# Power_PCB.net
KiCad netlist of a schematic drawn in Altium Designer
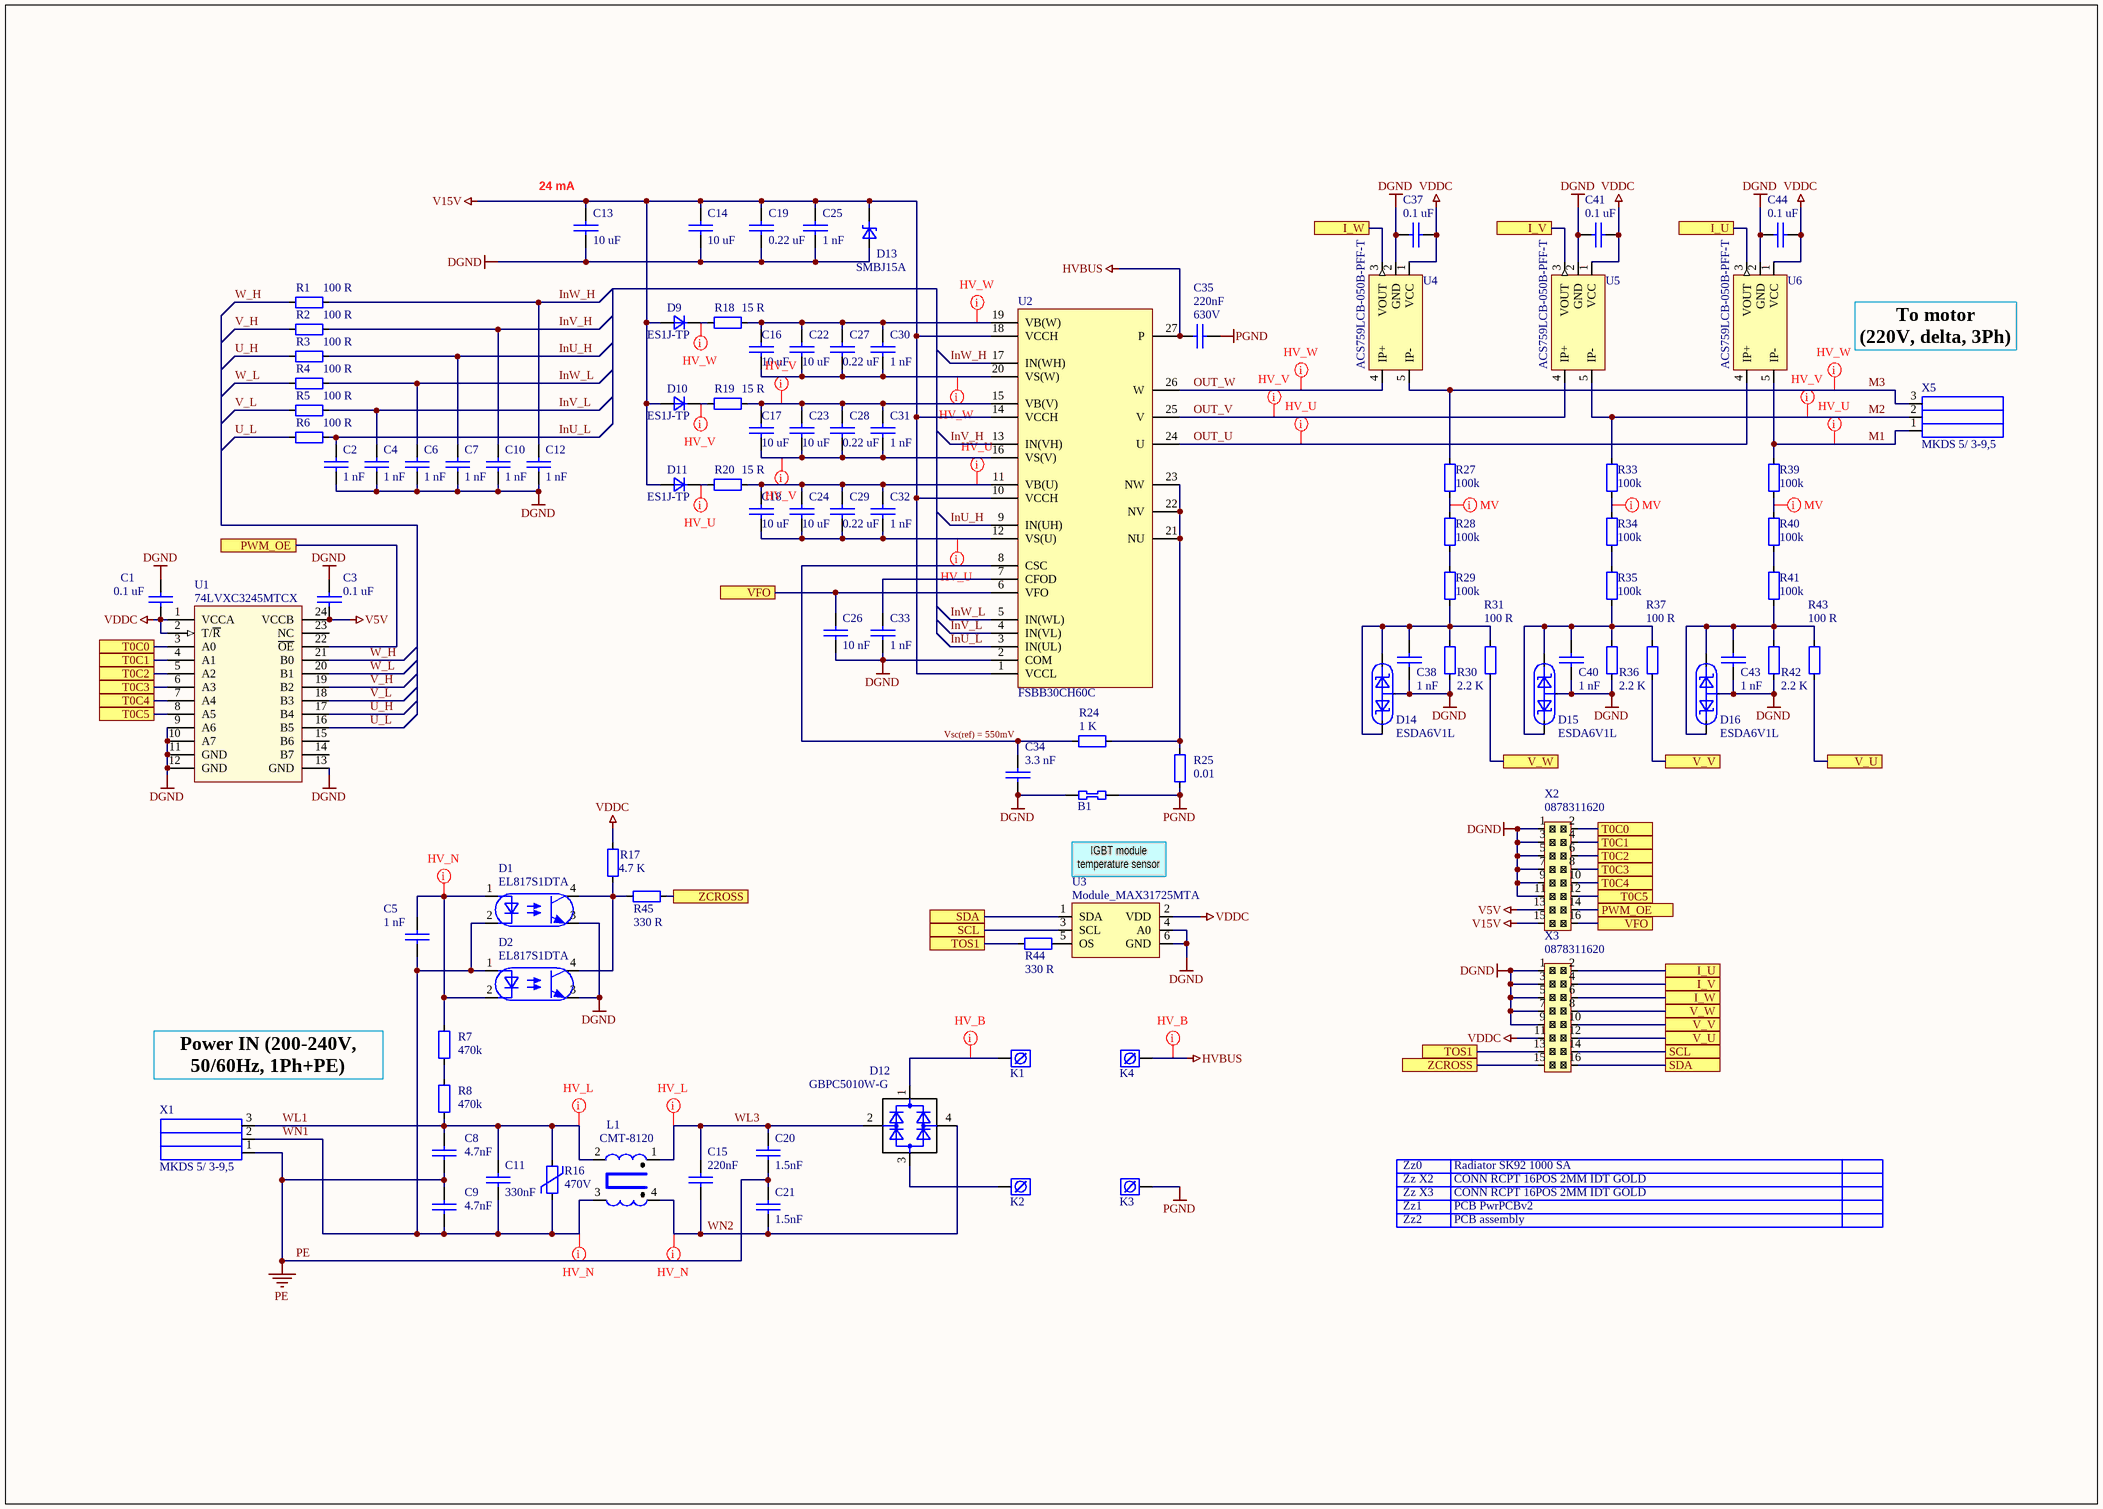
[diagram p0: Power_PCB.SchDoc]

(export (version "E")
  (design (tool "Eeschema 10.0.6"))
  (components
    (comp (ref "B1")
      (value "Net tie 2 mm")
      (footprint "Net tie 2 mm")
      (libsource (lib "ea_Mechanical") (part "Net tie 2 mm"))
    )
    (comp (ref "C1")
      (value "0.1 uF")
      (footprint "1608[0603]")
      (description "0.1 uF, 25V, 10% , X7R,  0603 SMD MLC Capacitor")
      (fields (field (name "TOLERANCE") "10%") (field (name "MANUFACTURER") "SAMSUNG"))
      (libsource (lib "ea_Capacitors") (part "CVNF100K0603-25"))
    )
    (comp (ref "C2")
      (value "1 nF")
      (footprint "1608[0603]")
      (description "1 nF, 50V, 10%, X7R, 0603 SMD MLC Capacitor")
      (fields (field (name "TOLERANCE") "10%") (field (name "MANUFACTURER") "SAMSUNG"))
      (libsource (lib "ea_Capacitors") (part "CVNF1.0K0603_1"))
    )
    (comp (ref "C3")
      (value "0.1 uF")
      (footprint "1608[0603]")
      (description "0.1 uF, 25V, 10% , X7R,  0603 SMD MLC Capacitor")
      (fields (field (name "TOLERANCE") "10%") (field (name "MANUFACTURER") "SAMSUNG"))
      (libsource (lib "ea_Capacitors") (part "CVNF100K0603-25"))
    )
    (comp (ref "C4")
      (value "1 nF")
      (footprint "1608[0603]")
      (description "1 nF, 50V, 10%, X7R, 0603 SMD MLC Capacitor")
      (fields (field (name "TOLERANCE") "10%") (field (name "MANUFACTURER") "SAMSUNG"))
      (libsource (lib "ea_Capacitors") (part "CVNF1.0K0603_1"))
    )
    (comp (ref "C5")
      (value "1 nF")
      (footprint "1608[0603]")
      (description "1 nF, 50V, 10%, X7R, 0603 SMD MLC Capacitor")
      (fields (field (name "TOLERANCE") "10%") (field (name "MANUFACTURER") "SAMSUNG"))
      (libsource (lib "ea_Capacitors") (part "CVNF1.0K0603_1"))
    )
    (comp (ref "C6")
      (value "1 nF")
      (footprint "1608[0603]")
      (description "1 nF, 50V, 10%, X7R, 0603 SMD MLC Capacitor")
      (fields (field (name "TOLERANCE") "10%") (field (name "MANUFACTURER") "SAMSUNG"))
      (libsource (lib "ea_Capacitors") (part "CVNF1.0K0603_1"))
    )
    (comp (ref "C7")
      (value "1 nF")
      (footprint "1608[0603]")
      (description "1 nF, 50V, 10%, X7R, 0603 SMD MLC Capacitor")
      (fields (field (name "TOLERANCE") "10%") (field (name "MANUFACTURER") "SAMSUNG"))
      (libsource (lib "ea_Capacitors") (part "CVNF1.0K0603_1"))
    )
    (comp (ref "C8")
      (value "4.7nF")
      (footprint "DE2E3KH472M")
      (description "CAP CER X1,Y2 4700PF 20% 250VAC,  THT 7.5mm; X1,Y2")
      (fields (field (name "MANUFACTURER") "Murata") (field (name "PARTNUM") "CMT-8120"))
      (libsource (lib "ea_Capacitors") (part "DE2E3KH472MA3B"))
    )
    (comp (ref "C9")
      (value "4.7nF")
      (footprint "DE2E3KH472M")
      (description "CAP CER X1,Y2 4700PF 20% 250VAC,  THT 7.5mm; X1,Y2")
      (fields (field (name "MANUFACTURER") "Murata") (field (name "PARTNUM") "CMT-8120"))
      (libsource (lib "ea_Capacitors") (part "DE2E3KH472MA3B"))
    )
    (comp (ref "C10")
      (value "1 nF")
      (footprint "1608[0603]")
      (description "1 nF, 50V, 10%, X7R, 0603 SMD MLC Capacitor")
      (fields (field (name "TOLERANCE") "10%") (field (name "MANUFACTURER") "SAMSUNG"))
      (libsource (lib "ea_Capacitors") (part "CVNF1.0K0603_1"))
    )
    (comp (ref "C11")
      (value "330nF")
      (footprint "JFV-330N/275-P15")
      (description "CAP X2, 330nF, 275V, ±10%; 18x10x15.8mm")
      (fields (field (name "MANUFACTURER") "JB CAPACITORS") (field (name "PARTNUM") "JFV-330N/275-P15"))
      (libsource (lib "ea_Capacitors") (part "JFV-330N/275-P15"))
    )
    (comp (ref "C12")
      (value "1 nF")
      (footprint "1608[0603]")
      (description "1 nF, 50V, 10%, X7R, 0603 SMD MLC Capacitor")
      (fields (field (name "TOLERANCE") "10%") (field (name "MANUFACTURER") "SAMSUNG"))
      (libsource (lib "ea_Capacitors") (part "CVNF1.0K0603_1"))
    )
    (comp (ref "C13")
      (value "10 uF")
      (footprint "3225[1210]")
      (description "10uF, 50V, 10%, X5R, -55..+85C, 1210")
      (fields (field (name "TOLERANCE") "10%") (field (name "MANUFACTURER") "Taiyo Yuden"))
      (libsource (lib "ea_Capacitors") (part "UMK325BJ106KM-T"))
    )
    (comp (ref "C14")
      (value "10 uF")
      (footprint "3225[1210]")
      (description "10uF, 50V, 10%, X5R, -55..+85C, 1210")
      (fields (field (name "TOLERANCE") "10%") (field (name "MANUFACTURER") "Taiyo Yuden"))
      (libsource (lib "ea_Capacitors") (part "UMK325BJ106KM-T"))
    )
    (comp (ref "C15")
      (value "220nF")
      (footprint "JFV-220N/275-P15")
      (description "CAP X2, 220nF; 15mm; ±10%; 18x6x12mm")
      (fields (field (name "MANUFACTURER") "JB CAPACITORS") (field (name "PARTNUM") "JFV-220N/275-P15"))
      (libsource (lib "ea_Capacitors") (part "JFV-220N/275-P15"))
    )
    (comp (ref "C16")
      (value "10 uF")
      (footprint "3225[1210]")
      (description "10uF, 50V, 10%, X5R, -55..+85C, 1210")
      (fields (field (name "TOLERANCE") "10%") (field (name "MANUFACTURER") "Taiyo Yuden"))
      (libsource (lib "ea_Capacitors") (part "UMK325BJ106KM-T"))
    )
    (comp (ref "C17")
      (value "10 uF")
      (footprint "3225[1210]")
      (description "10uF, 50V, 10%, X5R, -55..+85C, 1210")
      (fields (field (name "TOLERANCE") "10%") (field (name "MANUFACTURER") "Taiyo Yuden"))
      (libsource (lib "ea_Capacitors") (part "UMK325BJ106KM-T"))
    )
    (comp (ref "C18")
      (value "10 uF")
      (footprint "3225[1210]")
      (description "10uF, 50V, 10%, X5R, -55..+85C, 1210")
      (fields (field (name "TOLERANCE") "10%") (field (name "MANUFACTURER") "Taiyo Yuden"))
      (libsource (lib "ea_Capacitors") (part "UMK325BJ106KM-T"))
    )
    (comp (ref "C19")
      (value "0.22 uF")
      (footprint "2012[0805]")
      (description "0.22 uF, 50V, X7R,  0805")
      (fields (field (name "TOLERANCE") "+-10%") (field (name "MANUFACTURER") "Kemet"))
      (libsource (lib "ea_Capacitors") (part "C0805C224K5RACTU"))
    )
    (comp (ref "C20")
      (value "1.5nF")
      (footprint "CY2V-1N5")
      (description "CAP CER 1500PF 20% 250VAC,  THT 7.5mm;  dimeter 8mm, X1,Y2")
      (fields (field (name "PARTNUM") "CY2V-1N5") (field (name "TOLERANCE") "20%"))
      (libsource (lib "ea_Capacitors") (part "CY2V-1N5"))
    )
    (comp (ref "C21")
      (value "1.5nF")
      (footprint "CY2V-1N5")
      (description "CAP CER 1500PF 20% 250VAC,  THT 7.5mm;  dimeter 8mm, X1,Y2")
      (fields (field (name "PARTNUM") "CY2V-1N5") (field (name "TOLERANCE") "20%"))
      (libsource (lib "ea_Capacitors") (part "CY2V-1N5"))
    )
    (comp (ref "C22")
      (value "10 uF")
      (footprint "3225[1210]")
      (description "10uF, 50V, 10%, X5R, -55..+85C, 1210")
      (fields (field (name "TOLERANCE") "10%") (field (name "MANUFACTURER") "Taiyo Yuden"))
      (libsource (lib "ea_Capacitors") (part "UMK325BJ106KM-T"))
    )
    (comp (ref "C23")
      (value "10 uF")
      (footprint "3225[1210]")
      (description "10uF, 50V, 10%, X5R, -55..+85C, 1210")
      (fields (field (name "TOLERANCE") "10%") (field (name "MANUFACTURER") "Taiyo Yuden"))
      (libsource (lib "ea_Capacitors") (part "UMK325BJ106KM-T"))
    )
    (comp (ref "C24")
      (value "10 uF")
      (footprint "3225[1210]")
      (description "10uF, 50V, 10%, X5R, -55..+85C, 1210")
      (fields (field (name "TOLERANCE") "10%") (field (name "MANUFACTURER") "Taiyo Yuden"))
      (libsource (lib "ea_Capacitors") (part "UMK325BJ106KM-T"))
    )
    (comp (ref "C25")
      (value "1 nF")
      (footprint "1608[0603]")
      (description "1 nF, 50V, 10%, X7R, 0603 SMD MLC Capacitor")
      (fields (field (name "TOLERANCE") "10%") (field (name "MANUFACTURER") "SAMSUNG"))
      (libsource (lib "ea_Capacitors") (part "CVNF1.0K0603_1"))
    )
    (comp (ref "C26")
      (value "10 nF")
      (footprint "1608[0603]")
      (description "10 nF, 50V, 5%, X7R, 0603 SMD MLC Capacitor")
      (fields (field (name "TOLERANCE") "5%") (field (name "MANUFACTURER") "SAMSUNG"))
      (libsource (lib "ea_Capacitors") (part "CVNF010K0603"))
    )
    (comp (ref "C27")
      (value "0.22 uF")
      (footprint "2012[0805]")
      (description "0.22 uF, 50V, X7R,  0805")
      (fields (field (name "TOLERANCE") "+-10%") (field (name "MANUFACTURER") "Kemet"))
      (libsource (lib "ea_Capacitors") (part "C0805C224K5RACTU"))
    )
    (comp (ref "C28")
      (value "0.22 uF")
      (footprint "2012[0805]")
      (description "0.22 uF, 50V, X7R,  0805")
      (fields (field (name "TOLERANCE") "+-10%") (field (name "MANUFACTURER") "Kemet"))
      (libsource (lib "ea_Capacitors") (part "C0805C224K5RACTU"))
    )
    (comp (ref "C29")
      (value "0.22 uF")
      (footprint "2012[0805]")
      (description "0.22 uF, 50V, X7R,  0805")
      (fields (field (name "TOLERANCE") "+-10%") (field (name "MANUFACTURER") "Kemet"))
      (libsource (lib "ea_Capacitors") (part "C0805C224K5RACTU"))
    )
    (comp (ref "C30")
      (value "1 nF")
      (footprint "1608[0603]")
      (description "1 nF, 50V, 10%, X7R, 0603 SMD MLC Capacitor")
      (fields (field (name "TOLERANCE") "10%") (field (name "MANUFACTURER") "SAMSUNG"))
      (libsource (lib "ea_Capacitors") (part "CVNF1.0K0603_1"))
    )
    (comp (ref "C31")
      (value "1 nF")
      (footprint "1608[0603]")
      (description "1 nF, 50V, 10%, X7R, 0603 SMD MLC Capacitor")
      (fields (field (name "TOLERANCE") "10%") (field (name "MANUFACTURER") "SAMSUNG"))
      (libsource (lib "ea_Capacitors") (part "CVNF1.0K0603_1"))
    )
    (comp (ref "C32")
      (value "1 nF")
      (footprint "1608[0603]")
      (description "1 nF, 50V, 10%, X7R, 0603 SMD MLC Capacitor")
      (fields (field (name "TOLERANCE") "10%") (field (name "MANUFACTURER") "SAMSUNG"))
      (libsource (lib "ea_Capacitors") (part "CVNF1.0K0603_1"))
    )
    (comp (ref "C33")
      (value "1 nF")
      (footprint "1608[0603]")
      (description "1 nF, 50V, 10%, X7R, 0603 SMD MLC Capacitor")
      (fields (field (name "TOLERANCE") "10%") (field (name "MANUFACTURER") "SAMSUNG"))
      (libsource (lib "ea_Capacitors") (part "CVNF1.0K0603_1"))
    )
    (comp (ref "C34")
      (value "3.3 nF")
      (footprint "1608[0603]")
      (description "3.3 nF, 50V, 10%, X7R, 0603 SMD MLC Capacitor")
      (fields (field (name "MANUFACTURER") "SAMSUNG") (field (name "TOLERANCE") "10%"))
      (libsource (lib "ea_Capacitors") (part "CVNF3.3K0603_1"))
    )
    (comp (ref "C35")
      (value "220nF")
      (footprint "2220")
      (description "CAP 220NF. X7R, 630V, 2220, 5x5.7x2mm")
      (fields
        (field (name "MANUFACTURER") "Murata Electronics North America")
        (field (name "TOLERANCE") "10%")
        (field (name "VOLTAGE") "630V")
      )
      (libsource (lib "ea_Capacitors") (part "GRM55DR72J224KW01L"))
    )
    (comp (ref "C37")
      (value "0.1 uF")
      (footprint "1608[0603]")
      (description "0.1 uF, 25V, 10% , X7R,  0603 SMD MLC Capacitor")
      (fields (field (name "TOLERANCE") "10%") (field (name "MANUFACTURER") "SAMSUNG"))
      (libsource (lib "ea_Capacitors") (part "CVNF100K0603-25"))
    )
    (comp (ref "C38")
      (value "1 nF")
      (footprint "1608[0603]")
      (description "1 nF, 50V, 10%, X7R, 0603 SMD MLC Capacitor")
      (fields (field (name "TOLERANCE") "10%") (field (name "MANUFACTURER") "SAMSUNG"))
      (libsource (lib "ea_Capacitors") (part "CVNF1.0K0603_1"))
    )
    (comp (ref "C40")
      (value "1 nF")
      (footprint "1608[0603]")
      (description "1 nF, 50V, 10%, X7R, 0603 SMD MLC Capacitor")
      (fields (field (name "TOLERANCE") "10%") (field (name "MANUFACTURER") "SAMSUNG"))
      (libsource (lib "ea_Capacitors") (part "CVNF1.0K0603_1"))
    )
    (comp (ref "C41")
      (value "0.1 uF")
      (footprint "1608[0603]")
      (description "0.1 uF, 25V, 10% , X7R,  0603 SMD MLC Capacitor")
      (fields (field (name "TOLERANCE") "10%") (field (name "MANUFACTURER") "SAMSUNG"))
      (libsource (lib "ea_Capacitors") (part "CVNF100K0603-25"))
    )
    (comp (ref "C43")
      (value "1 nF")
      (footprint "1608[0603]")
      (description "1 nF, 50V, 10%, X7R, 0603 SMD MLC Capacitor")
      (fields (field (name "TOLERANCE") "10%") (field (name "MANUFACTURER") "SAMSUNG"))
      (libsource (lib "ea_Capacitors") (part "CVNF1.0K0603_1"))
    )
    (comp (ref "C44")
      (value "0.1 uF")
      (footprint "1608[0603]")
      (description "0.1 uF, 25V, 10% , X7R,  0603 SMD MLC Capacitor")
      (fields (field (name "TOLERANCE") "10%") (field (name "MANUFACTURER") "SAMSUNG"))
      (libsource (lib "ea_Capacitors") (part "CVNF100K0603-25"))
    )
    (comp (ref "D1")
      (value "EL817S1DTA")
      (footprint "Optoc EL816")
      (description "Optoc.  5mA >300%, 5kV, SMD4")
      (fields (field (name "MANUFACTURER") "EVERLIGHT") (field (name "PARTNUM") "638-EL817S1DTA"))
      (libsource (lib "ea_Opto") (part "EL817S1DTA"))
    )
    (comp (ref "D2")
      (value "EL817S1DTA")
      (footprint "Optoc EL816")
      (description "Optoc.  5mA >300%, 5kV, SMD4")
      (fields (field (name "MANUFACTURER") "EVERLIGHT") (field (name "PARTNUM") "638-EL817S1DTA"))
      (libsource (lib "ea_Opto") (part "EL817S1DTA"))
    )
    (comp (ref "D9")
      (value "ES1J-TP")
      (footprint "DO-214AA_SMBJ")
      (description "DIODE FAST REC 600V 1A DO214AC")
      (fields (field (name "MANUFACTURER") "Micro Commercial Co") (field (name "PARTNUM") "ES1J-TPCT-ND"))
      (libsource (lib "ea_Diodes") (part "ES1J-TP"))
    )
    (comp (ref "D10")
      (value "ES1J-TP")
      (footprint "DO-214AA_SMBJ")
      (description "DIODE FAST REC 600V 1A DO214AC")
      (fields (field (name "MANUFACTURER") "Micro Commercial Co") (field (name "PARTNUM") "ES1J-TPCT-ND"))
      (libsource (lib "ea_Diodes") (part "ES1J-TP"))
    )
    (comp (ref "D11")
      (value "ES1J-TP")
      (footprint "DO-214AA_SMBJ")
      (description "DIODE FAST REC 600V 1A DO214AC")
      (fields (field (name "MANUFACTURER") "Micro Commercial Co") (field (name "PARTNUM") "ES1J-TPCT-ND"))
      (libsource (lib "ea_Diodes") (part "ES1J-TP"))
    )
    (comp (ref "D12")
      (value "GBPC5010W-G")
      (footprint "GBPC5010W")
      (description "Bridge rectifier; 1000V; 50A; 450Amax, wire 1.07mm")
      (fields (field (name "MANUFACTURER") "Comchip Technology") (field (name "PARTNUM") "641-1389-ND"))
      (libsource (lib "ea_Diode_bridges") (part "GBPC5010W-G"))
    )
    (comp (ref "D13")
      (value "SMBJ15A")
      (footprint "SMB ST")
      (description "DIODE TVS 15V 600W UNI 5% SMD")
      (fields (field (name "MANUFACTURER") "TAIWAN SEMICONDUCTOR") (field (name "PARTNUM") "7277733RL"))
      (libsource (lib "ea_TVS_protection") (part "SMBJ15A"))
    )
    (comp (ref "D14")
      (value "ESDA6V1L")
      (footprint "SOT23")
      (description "Dual transil array for ESD, 6.1 V, 300 W")
      (fields (field (name "MANUFACTURER") "Micro Commercial Co") (field (name "PARTNUM") "ESDA6V1L-TPCT-ND"))
      (libsource (lib "*") (part "ESDA6V1L"))
    )
    (comp (ref "D15")
      (value "ESDA6V1L")
      (footprint "SOT23")
      (description "Dual transil array for ESD, 6.1 V, 300 W")
      (fields (field (name "MANUFACTURER") "Micro Commercial Co") (field (name "PARTNUM") "ESDA6V1L-TPCT-ND"))
      (libsource (lib "*") (part "ESDA6V1L"))
    )
    (comp (ref "D16")
      (value "ESDA6V1L")
      (footprint "SOT23")
      (description "Dual transil array for ESD, 6.1 V, 300 W")
      (fields (field (name "MANUFACTURER") "Micro Commercial Co") (field (name "PARTNUM") "ESDA6V1L-TPCT-ND"))
      (libsource (lib "*") (part "ESDA6V1L"))
    )
    (comp (ref "K1")
      (value "KEYS7692")
      (footprint "KEYS7692")
      (description "Screw terminal KEYS7692")
      (fields (field (name "MANUFACTURER") "KEYSTONE"))
      (libsource (lib "Inverter_v2") (part "KEYS7692"))
    )
    (comp (ref "K2")
      (value "KEYS7692")
      (footprint "KEYS7692")
      (description "Screw terminal KEYS7692")
      (fields (field (name "MANUFACTURER") "KEYSTONE"))
      (libsource (lib "Inverter_v2") (part "KEYS7692"))
    )
    (comp (ref "K3")
      (value "KEYS7692")
      (footprint "KEYS7692")
      (description "Screw terminal KEYS7692")
      (fields (field (name "MANUFACTURER") "KEYSTONE"))
      (libsource (lib "Inverter_v2") (part "KEYS7692"))
    )
    (comp (ref "K4")
      (value "KEYS7692")
      (footprint "KEYS7692")
      (description "Screw terminal KEYS7692")
      (fields (field (name "MANUFACTURER") "KEYSTONE"))
      (libsource (lib "Inverter_v2") (part "KEYS7692"))
    )
    (comp (ref "L1")
      (value "CMT-8120")
      (footprint "CMT-8120")
      (description "INDUCTOR 2.4MH COMMON MODE VERT, 17A")
      (fields (field (name "MANUFACTURER") "Triad Magnetics") (field (name "PARTNUM") "237-1373-ND"))
      (libsource (lib "ea_Inductors") (part "CMT-8120"))
    )
    (comp (ref "R1")
      (value "100 R")
      (footprint "0603")
      (description "100 R, 1%, 0603, SMD Resistor, Taped")
      (fields (field (name "MANUFACTURER") "PANASONIC") (field (name "TOLERANCE") "1%"))
      (libsource (lib "ea_Resistors") (part "RL0603E100-1_1"))
    )
    (comp (ref "R2")
      (value "100 R")
      (footprint "0603")
      (description "100 R, 1%, 0603, SMD Resistor, Taped")
      (fields (field (name "MANUFACTURER") "PANASONIC") (field (name "TOLERANCE") "1%"))
      (libsource (lib "ea_Resistors") (part "RL0603E100-1_1"))
    )
    (comp (ref "R3")
      (value "100 R")
      (footprint "0603")
      (description "100 R, 1%, 0603, SMD Resistor, Taped")
      (fields (field (name "MANUFACTURER") "PANASONIC") (field (name "TOLERANCE") "1%"))
      (libsource (lib "ea_Resistors") (part "RL0603E100-1_1"))
    )
    (comp (ref "R4")
      (value "100 R")
      (footprint "0603")
      (description "100 R, 1%, 0603, SMD Resistor, Taped")
      (fields (field (name "MANUFACTURER") "PANASONIC") (field (name "TOLERANCE") "1%"))
      (libsource (lib "ea_Resistors") (part "RL0603E100-1_1"))
    )
    (comp (ref "R5")
      (value "100 R")
      (footprint "0603")
      (description "100 R, 1%, 0603, SMD Resistor, Taped")
      (fields (field (name "MANUFACTURER") "PANASONIC") (field (name "TOLERANCE") "1%"))
      (libsource (lib "ea_Resistors") (part "RL0603E100-1_1"))
    )
    (comp (ref "R6")
      (value "100 R")
      (footprint "0603")
      (description "100 R, 1%, 0603, SMD Resistor, Taped")
      (fields (field (name "MANUFACTURER") "PANASONIC") (field (name "TOLERANCE") "1%"))
      (libsource (lib "ea_Resistors") (part "RL0603E100-1_1"))
    )
    (comp (ref "R7")
      (value "470k")
      (footprint "CR6332-2512")
      (description "470k, 2512, 1W; 200V, ±1%; -55 125°C")
      (fields (field (name "MANUFACTURER") "ROYAL OHM") (field (name "PARTNUM") "25121WF0474T4E"))
      (libsource (lib "ea_Resistors") (part "25121WF0474T4E"))
    )
    (comp (ref "R8")
      (value "470k")
      (footprint "CR6332-2512")
      (description "470k, 2512, 1W; 200V, ±1%; -55 125°C")
      (fields (field (name "MANUFACTURER") "ROYAL OHM") (field (name "PARTNUM") "25121WF0474T4E"))
      (libsource (lib "ea_Resistors") (part "25121WF0474T4E"))
    )
    (comp (ref "R16")
      (value "ERZV14D471")
      (footprint "ERZ-V14D471")
      (description "VARISTOR Disc 14mm, 6kA, 175J,")
      (fields (field (name "MANUFACTURER") "PANASONIC") (field (name "VOLTAGE") "470V"))
      (libsource (lib "ea_TVS_protection") (part "ERZV14D471"))
    )
    (comp (ref "R17")
      (value "4.7 K")
      (footprint "0603")
      (description "4.7 K, 1%, 0603, SMD Resistor, Taped")
      (fields (field (name "MANUFACTURER") "YAGEO AMERICA CORPORATION") (field (name "TOLERANCE") "1%"))
      (libsource (lib "ea_Resistors") (part "RL0603K004.7-1_1"))
    )
    (comp (ref "R18")
      (value "15 R")
      (footprint "3216[1206]")
      (description "15 R, 1%,  0.25 W, 200 V, 1206")
      (fields (field (name "MANUFACTURER") "Vishay") (field (name "TOLERANCE") "1%"))
      (libsource (lib "ea_Resistors") (part "RL1206E015-1"))
    )
    (comp (ref "R19")
      (value "15 R")
      (footprint "3216[1206]")
      (description "15 R, 1%,  0.25 W, 200 V, 1206")
      (fields (field (name "MANUFACTURER") "Vishay") (field (name "TOLERANCE") "1%"))
      (libsource (lib "ea_Resistors") (part "RL1206E015-1"))
    )
    (comp (ref "R20")
      (value "15 R")
      (footprint "3216[1206]")
      (description "15 R, 1%,  0.25 W, 200 V, 1206")
      (fields (field (name "MANUFACTURER") "Vishay") (field (name "TOLERANCE") "1%"))
      (libsource (lib "ea_Resistors") (part "RL1206E015-1"))
    )
    (comp (ref "R24")
      (value "1 K")
      (footprint "0603")
      (description "1 K, 1%, 0603, SMD Resistor, Taped")
      (fields (field (name "MANUFACTURER") "YAGEO AMERICA CORPORATION") (field (name "TOLERANCE") "1%"))
      (libsource (lib "ea_Resistors") (part "RL0603K001-1_1"))
    )
    (comp (ref "R25")
      (value "0.01")
      (footprint "MCS3264")
      (description "Curr.sens.res. 0.01 OHM 2W 1% , 2512 (6432 Metric)")
      (fields (field (name "MANUFACTURER") "Ohmite") (field (name "TOLERANCE") "1%"))
      (libsource (lib "ea_Resistors") (part "MCS3264R010FER"))
    )
    (comp (ref "R27")
      (value "100k")
      (footprint "3216[1206]")
      (description "100K, 1%,  1206,  200v,  SMD 1206")
      (fields (field (name "MANUFACTURER") "Panasonic") (field (name "PARTNUM") "ERJ-8ENF1003V"))
      (libsource (lib "ea_Resistors") (part "RL1206K100-1"))
    )
    (comp (ref "R28")
      (value "100k")
      (footprint "3216[1206]")
      (description "100K, 1%,  1206,  200v,  SMD 1206")
      (fields (field (name "MANUFACTURER") "Panasonic") (field (name "PARTNUM") "ERJ-8ENF1003V"))
      (libsource (lib "ea_Resistors") (part "RL1206K100-1"))
    )
    (comp (ref "R29")
      (value "100k")
      (footprint "3216[1206]")
      (description "100K, 1%,  1206,  200v,  SMD 1206")
      (fields (field (name "MANUFACTURER") "Panasonic") (field (name "PARTNUM") "ERJ-8ENF1003V"))
      (libsource (lib "ea_Resistors") (part "RL1206K100-1"))
    )
    (comp (ref "R30")
      (value "2.2 K")
      (footprint "0603")
      (description "2.2 K, 1%, 0603, SMD Resistor, Taped")
      (fields (field (name "MANUFACTURER") "YAGEO AMERICA CORPORATION") (field (name "TOLERANCE") "1%"))
      (libsource (lib "ea_Resistors") (part "RL0603K002.2-1_1"))
    )
    (comp (ref "R31")
      (value "100 R")
      (footprint "0603")
      (description "100 R, 1%, 0603, SMD Resistor, Taped")
      (fields (field (name "MANUFACTURER") "PANASONIC") (field (name "TOLERANCE") "1%"))
      (libsource (lib "") (part "RL0603E100-1_1_1"))
    )
    (comp (ref "R33")
      (value "100k")
      (footprint "3216[1206]")
      (description "100K, 1%,  1206,  200v,  SMD 1206")
      (fields (field (name "MANUFACTURER") "Panasonic") (field (name "PARTNUM") "ERJ-8ENF1003V"))
      (libsource (lib "ea_Resistors") (part "RL1206K100-1"))
    )
    (comp (ref "R34")
      (value "100k")
      (footprint "3216[1206]")
      (description "100K, 1%,  1206,  200v,  SMD 1206")
      (fields (field (name "MANUFACTURER") "Panasonic") (field (name "PARTNUM") "ERJ-8ENF1003V"))
      (libsource (lib "ea_Resistors") (part "RL1206K100-1"))
    )
    (comp (ref "R35")
      (value "100k")
      (footprint "3216[1206]")
      (description "100K, 1%,  1206,  200v,  SMD 1206")
      (fields (field (name "MANUFACTURER") "Panasonic") (field (name "PARTNUM") "ERJ-8ENF1003V"))
      (libsource (lib "ea_Resistors") (part "RL1206K100-1"))
    )
    (comp (ref "R36")
      (value "2.2 K")
      (footprint "0603")
      (description "2.2 K, 1%, 0603, SMD Resistor, Taped")
      (fields (field (name "MANUFACTURER") "YAGEO AMERICA CORPORATION") (field (name "TOLERANCE") "1%"))
      (libsource (lib "ea_Resistors") (part "RL0603K002.2-1_1"))
    )
    (comp (ref "R37")
      (value "100 R")
      (footprint "0603")
      (description "100 R, 1%, 0603, SMD Resistor, Taped")
      (fields (field (name "MANUFACTURER") "PANASONIC") (field (name "TOLERANCE") "1%"))
      (libsource (lib "") (part "RL0603E100-1_1_1"))
    )
    (comp (ref "R39")
      (value "100k")
      (footprint "3216[1206]")
      (description "100K, 1%,  1206,  200v,  SMD 1206")
      (fields (field (name "MANUFACTURER") "Panasonic") (field (name "PARTNUM") "ERJ-8ENF1003V"))
      (libsource (lib "ea_Resistors") (part "RL1206K100-1"))
    )
    (comp (ref "R40")
      (value "100k")
      (footprint "3216[1206]")
      (description "100K, 1%,  1206,  200v,  SMD 1206")
      (fields (field (name "MANUFACTURER") "Panasonic") (field (name "PARTNUM") "ERJ-8ENF1003V"))
      (libsource (lib "ea_Resistors") (part "RL1206K100-1"))
    )
    (comp (ref "R41")
      (value "100k")
      (footprint "3216[1206]")
      (description "100K, 1%,  1206,  200v,  SMD 1206")
      (fields (field (name "MANUFACTURER") "Panasonic") (field (name "PARTNUM") "ERJ-8ENF1003V"))
      (libsource (lib "ea_Resistors") (part "RL1206K100-1"))
    )
    (comp (ref "R42")
      (value "2.2 K")
      (footprint "0603")
      (description "2.2 K, 1%, 0603, SMD Resistor, Taped")
      (fields (field (name "MANUFACTURER") "YAGEO AMERICA CORPORATION") (field (name "TOLERANCE") "1%"))
      (libsource (lib "ea_Resistors") (part "RL0603K002.2-1_1"))
    )
    (comp (ref "R43")
      (value "100 R")
      (footprint "0603")
      (description "100 R, 1%, 0603, SMD Resistor, Taped")
      (fields (field (name "MANUFACTURER") "PANASONIC") (field (name "TOLERANCE") "1%"))
      (libsource (lib "") (part "RL0603E100-1_1_1"))
    )
    (comp (ref "R44")
      (value "330 R")
      (footprint "0603")
      (description "330 R, 1%, 0603, SMD Resistor, Taped")
      (fields (field (name "MANUFACTURER") "YAGEO AMERICA CORPORATION") (field (name "TOLERANCE") "1%"))
      (libsource (lib "ea_Resistors") (part "RL0603E330-1_1"))
    )
    (comp (ref "R45")
      (value "330 R")
      (footprint "0603")
      (description "330 R, 1%, 0603, SMD Resistor, Taped")
      (fields (field (name "MANUFACTURER") "YAGEO AMERICA CORPORATION") (field (name "TOLERANCE") "1%"))
      (libsource (lib "ea_Resistors") (part "RL0603E330-1_1"))
    )
    (comp (ref "U1")
      (value "74LVXC3245MTCX")
      (footprint "TSSOP24 , JEDEC MO-153, Fairchild")
      (description "TXRX 8BIT DUAL CONF VOLT 24TSSOP")
      (fields (field (name "MANUFACTURER") "FAIRCHILD") (field (name "PARTNUM") "74LVXC3245MTCXCT-ND"))
      (libsource (lib "ea_IC_registers_buffers") (part "74LVXC3245MTCX"))
    )
    (comp (ref "U2")
      (value "FSBB30CH60C")
      (footprint "FSSB30CH60C")
      (description "IGBT module, 600V, 30A, Vcesat 2.0V, 20kHz, SPM27-double DIP")
      (fields (field (name "MANUFACTURER") "Infineon"))
      (libsource (lib "ea_MOSFET_&_drivers") (part "FSBB30CH60C"))
    )
    (comp (ref "U3")
      (value "Module_MAX31725MTA")
      (footprint "TempSensor on MAX31725")
      (description "IC TEMP SENSOR 8-TDFN")
      (fields (field (name "MANUFACTURER") "Barduva"))
      (libsource (lib "ea_IC_sensors") (part "Module_MAX31725MTA"))
    )
    (comp (ref "U4")
      (value "ACS759LCB-050B-PFF-T")
      (footprint "ACS756")
      (description "IC HALL EFFECT SENSOR 50A, 3V")
      (fields
        (field (name "MANUFACTURER") "Allegro Microsystems Inc")
        (field (name "PARTNUM") "620-1467-5-ND")
      )
      (libsource (lib "ea_IC_sensors") (part "ACS759LCB-050B-PFF-T"))
    )
    (comp (ref "U5")
      (value "ACS759LCB-050B-PFF-T")
      (footprint "ACS756")
      (description "IC HALL EFFECT SENSOR 50A, 3V")
      (fields
        (field (name "MANUFACTURER") "Allegro Microsystems Inc")
        (field (name "PARTNUM") "620-1467-5-ND")
      )
      (libsource (lib "ea_IC_sensors") (part "ACS759LCB-050B-PFF-T"))
    )
    (comp (ref "U6")
      (value "ACS759LCB-050B-PFF-T")
      (footprint "ACS756")
      (description "IC HALL EFFECT SENSOR 50A, 3V")
      (fields
        (field (name "MANUFACTURER") "Allegro Microsystems Inc")
        (field (name "PARTNUM") "620-1467-5-ND")
      )
      (libsource (lib "ea_IC_sensors") (part "ACS759LCB-050B-PFF-T"))
    )
    (comp (ref "X1")
      (value "MKDS 5/ 3-9,5")
      (footprint "MKDS 5/ 3-9,5")
      (description "HEADER, VERTICAL, 9.52MM, 3WAY, 32A, 1000V")
      (fields (field (name "MANUFACTURER") "PHOENIX CONTACT") (field (name "PARTNUM") "1714984"))
      (libsource (lib "ea_Connectors") (part "MKDS 5/ 3-9,5"))
    )
    (comp (ref "X2")
      (value "0878311620")
      (footprint "8x2, 2.00mm Pitch Milli-Grid™ Header, Molex")
      (description "CONN HEADER 16POS 2MM VERT GOLD")
      (fields (field (name "MANUFACTURER") "Molex") (field (name "PARTNUM") "WM18562-ND"))
      (libsource (lib "ea_Connectors") (part "0878311620"))
    )
    (comp (ref "X3")
      (value "0878311620")
      (footprint "8x2, 2.00mm Pitch Milli-Grid™ Header, Molex")
      (description "CONN HEADER 16POS 2MM VERT GOLD")
      (fields (field (name "MANUFACTURER") "Molex") (field (name "PARTNUM") "WM18562-ND"))
      (libsource (lib "ea_Connectors") (part "0878311620"))
    )
    (comp (ref "X5")
      (value "MKDS 5/ 3-9,5")
      (footprint "MKDS 5/ 3-9,5")
      (description "HEADER, VERTICAL, 9.52MM, 3WAY, 32A, 1000V")
      (fields (field (name "MANUFACTURER") "PHOENIX CONTACT") (field (name "PARTNUM") "1714984"))
      (libsource (lib "ea_Connectors") (part "MKDS 5/ 3-9,5"))
    )
    (comp (ref "Zz X2")
      (value "CONN RCPT 16POS 2MM IDT GOLD")
      (fields (field (name "MANUFACTURER") "Molex Inc") (field (name "PARTNUM") "WM8606-ND"))
      (libsource (lib "ea_Mechanical") (part "BOM item"))
    )
    (comp (ref "Zz X3")
      (value "CONN RCPT 16POS 2MM IDT GOLD")
      (fields (field (name "MANUFACTURER") "Molex Inc") (field (name "PARTNUM") "WM8606-ND"))
      (libsource (lib "ea_Mechanical") (part "BOM item"))
    )
    (comp (ref "Zz0")
      (value "Radiator SK92 1000 SA")
      (fields (field (name "MANUFACTURER") "FISCHER ELEKTRONIK"))
      (libsource (lib "ea_Mechanical") (part "BOM item"))
    )
    (comp (ref "Zz1")
      (value "PCB PwrPCBv2")
      (fields (field (name "MANUFACTURER") "Brandner") (field (name "PARTNUM") "PwrPCBv2 board"))
      (libsource (lib "ea_Mechanical") (part "BOM item"))
    )
    (comp (ref "Zz2")
      (value "PCB assembly")
      (fields (field (name "MANUFACTURER") "ESEMDA") (field (name "PARTNUM") "PwrPCBv2 assembly"))
      (libsource (lib "ea_Mechanical") (part "BOM item"))
    )
  )
  (nets
    (net (code "1") (name "/I_U") (class "Default")
      (node (ref "U6") (pin "3") (pinfunction "VOUT_3") (pintype "output"))
      (node (ref "X3") (pin "2") (pinfunction "2_2") (pintype "passive"))
    )
    (net (code "2") (name "/I_V") (class "Default")
      (node (ref "U5") (pin "3") (pinfunction "VOUT_3") (pintype "output"))
      (node (ref "X3") (pin "4") (pinfunction "4_4") (pintype "passive"))
    )
    (net (code "3") (name "/I_W") (class "Default")
      (node (ref "U4") (pin "3") (pinfunction "VOUT_3") (pintype "output"))
      (node (ref "X3") (pin "6") (pinfunction "6_6") (pintype "passive"))
    )
    (net (code "4") (name "/InU_H") (class "Default")
      (node (ref "C7") (pin "1") (pinfunction "1_1") (pintype "passive"))
      (node (ref "R3") (pin "1") (pinfunction "1_1") (pintype "passive"))
      (node (ref "U2") (pin "9") (pinfunction "IN(UH)_9") (pintype "passive"))
    )
    (net (code "5") (name "/InU_L") (class "Default")
      (node (ref "C2") (pin "1") (pinfunction "1_1") (pintype "passive"))
      (node (ref "R6") (pin "1") (pinfunction "1_1") (pintype "passive"))
      (node (ref "U2") (pin "3") (pinfunction "IN(UL)_3") (pintype "passive"))
    )
    (net (code "6") (name "/InV_H") (class "Default")
      (node (ref "C10") (pin "1") (pinfunction "1_1") (pintype "passive"))
      (node (ref "R2") (pin "1") (pinfunction "1_1") (pintype "passive"))
      (node (ref "U2") (pin "13") (pinfunction "IN(VH)_13") (pintype "passive"))
    )
    (net (code "7") (name "/InV_L") (class "Default")
      (node (ref "C4") (pin "1") (pinfunction "1_1") (pintype "passive"))
      (node (ref "R5") (pin "1") (pinfunction "1_1") (pintype "passive"))
      (node (ref "U2") (pin "4") (pinfunction "IN(VL)_4") (pintype "passive"))
    )
    (net (code "8") (name "/InW_H") (class "Default")
      (node (ref "C12") (pin "1") (pinfunction "1_1") (pintype "passive"))
      (node (ref "R1") (pin "1") (pinfunction "1_1") (pintype "passive"))
      (node (ref "U2") (pin "17") (pinfunction "IN(WH)_17") (pintype "passive"))
    )
    (net (code "9") (name "/InW_L") (class "Default")
      (node (ref "C6") (pin "1") (pinfunction "1_1") (pintype "passive"))
      (node (ref "R4") (pin "1") (pinfunction "1_1") (pintype "passive"))
      (node (ref "U2") (pin "5") (pinfunction "IN(WL)_5") (pintype "passive"))
    )
    (net (code "10") (name "/M1") (class "Default")
      (node (ref "R39") (pin "1") (pinfunction "1_1") (pintype "passive"))
      (node (ref "U6") (pin "5") (pinfunction "IP-_5") (pintype "passive"))
      (node (ref "X5") (pin "1") (pinfunction "1_1") (pintype "passive"))
    )
    (net (code "11") (name "/M2") (class "Default")
      (node (ref "R33") (pin "1") (pinfunction "1_1") (pintype "passive"))
      (node (ref "U5") (pin "5") (pinfunction "IP-_5") (pintype "passive"))
      (node (ref "X5") (pin "2") (pinfunction "2_2") (pintype "passive"))
    )
    (net (code "12") (name "/M3") (class "Default")
      (node (ref "R27") (pin "1") (pinfunction "1_1") (pintype "passive"))
      (node (ref "U4") (pin "5") (pinfunction "IP-_5") (pintype "passive"))
      (node (ref "X5") (pin "3") (pinfunction "3_3") (pintype "passive"))
    )
    (net (code "13") (name "/OUT_U") (class "Default")
      (node (ref "U2") (pin "24") (pinfunction "U_24") (pintype "passive"))
      (node (ref "U6") (pin "4") (pinfunction "IP+_4") (pintype "passive"))
    )
    (net (code "14") (name "/OUT_V") (class "Default")
      (node (ref "U2") (pin "25") (pinfunction "V_25") (pintype "passive"))
      (node (ref "U5") (pin "4") (pinfunction "IP+_4") (pintype "passive"))
    )
    (net (code "15") (name "/OUT_W") (class "Default")
      (node (ref "U2") (pin "26") (pinfunction "W_26") (pintype "passive"))
      (node (ref "U4") (pin "4") (pinfunction "IP+_4") (pintype "passive"))
    )
    (net (code "16") (name "/PWM_OE") (class "Default")
      (node (ref "U1") (pin "22") (pinfunction "~{OE}_22") (pintype "passive"))
      (node (ref "X2") (pin "14") (pinfunction "14_14") (pintype "passive"))
    )
    (net (code "17") (name "/SCL") (class "Default")
      (node (ref "U3") (pin "3") (pinfunction "SCL_3") (pintype "passive"))
      (node (ref "X3") (pin "14") (pinfunction "14_14") (pintype "passive"))
    )
    (net (code "18") (name "/SDA") (class "Default")
      (node (ref "U3") (pin "1") (pinfunction "SDA_1") (pintype "passive"))
      (node (ref "X3") (pin "16") (pinfunction "16_16") (pintype "passive"))
    )
    (net (code "19") (name "/T0C0") (class "Default")
      (node (ref "U1") (pin "3") (pinfunction "A0_3") (pintype "passive"))
      (node (ref "X2") (pin "2") (pinfunction "2_2") (pintype "passive"))
    )
    (net (code "20") (name "/T0C1") (class "Default")
      (node (ref "U1") (pin "4") (pinfunction "A1_4") (pintype "passive"))
      (node (ref "X2") (pin "4") (pinfunction "4_4") (pintype "passive"))
    )
    (net (code "21") (name "/T0C2") (class "Default")
      (node (ref "U1") (pin "5") (pinfunction "A2_5") (pintype "passive"))
      (node (ref "X2") (pin "6") (pinfunction "6_6") (pintype "passive"))
    )
    (net (code "22") (name "/T0C3") (class "Default")
      (node (ref "U1") (pin "6") (pinfunction "A3_6") (pintype "passive"))
      (node (ref "X2") (pin "8") (pinfunction "8_8") (pintype "passive"))
    )
    (net (code "23") (name "/T0C4") (class "Default")
      (node (ref "U1") (pin "7") (pinfunction "A4_7") (pintype "passive"))
      (node (ref "X2") (pin "10") (pinfunction "10_10") (pintype "passive"))
    )
    (net (code "24") (name "/T0C5") (class "Default")
      (node (ref "U1") (pin "8") (pinfunction "A5_8") (pintype "passive"))
      (node (ref "X2") (pin "12") (pinfunction "12_12") (pintype "passive"))
    )
    (net (code "25") (name "/TOS1") (class "Default")
      (node (ref "R44") (pin "2") (pinfunction "2_2") (pintype "passive"))
      (node (ref "X3") (pin "13") (pinfunction "13_13") (pintype "passive"))
    )
    (net (code "26") (name "/U_H") (class "Default")
      (node (ref "R3") (pin "2") (pinfunction "2_2") (pintype "passive"))
      (node (ref "U1") (pin "17") (pinfunction "B4_17") (pintype "passive"))
    )
    (net (code "27") (name "/U_L") (class "Default")
      (node (ref "R6") (pin "2") (pinfunction "2_2") (pintype "passive"))
      (node (ref "U1") (pin "16") (pinfunction "B5_16") (pintype "passive"))
    )
    (net (code "28") (name "/VFO") (class "Default")
      (node (ref "C26") (pin "2") (pinfunction "2_2") (pintype "passive"))
      (node (ref "U2") (pin "6") (pinfunction "VFO_6") (pintype "passive"))
      (node (ref "X2") (pin "16") (pinfunction "16_16") (pintype "passive"))
    )
    (net (code "29") (name "/V_H") (class "Default")
      (node (ref "R2") (pin "2") (pinfunction "2_2") (pintype "passive"))
      (node (ref "U1") (pin "19") (pinfunction "B2_19") (pintype "passive"))
    )
    (net (code "30") (name "/V_L") (class "Default")
      (node (ref "R5") (pin "2") (pinfunction "2_2") (pintype "passive"))
      (node (ref "U1") (pin "18") (pinfunction "B3_18") (pintype "passive"))
    )
    (net (code "31") (name "/V_U") (class "Default")
      (node (ref "R43") (pin "2") (pinfunction "2_2") (pintype "passive"))
      (node (ref "X3") (pin "12") (pinfunction "12_12") (pintype "passive"))
    )
    (net (code "32") (name "/V_V") (class "Default")
      (node (ref "R37") (pin "2") (pinfunction "2_2") (pintype "passive"))
      (node (ref "X3") (pin "10") (pinfunction "10_10") (pintype "passive"))
    )
    (net (code "33") (name "/V_W") (class "Default")
      (node (ref "R31") (pin "2") (pinfunction "2_2") (pintype "passive"))
      (node (ref "X3") (pin "8") (pinfunction "8_8") (pintype "passive"))
    )
    (net (code "34") (name "/WL1") (class "Default")
      (node (ref "C11") (pin "1") (pinfunction "1_1") (pintype "passive"))
      (node (ref "C8") (pin "1") (pinfunction "1_1") (pintype "passive"))
      (node (ref "L1") (pin "2") (pinfunction "2_2") (pintype "passive"))
      (node (ref "R16") (pin "2") (pinfunction "2_2") (pintype "passive"))
      (node (ref "R8") (pin "1") (pinfunction "1_1") (pintype "passive"))
      (node (ref "X1") (pin "3") (pinfunction "3_3") (pintype "passive"))
    )
    (net (code "35") (name "/WL3") (class "Default")
      (node (ref "C15") (pin "1") (pinfunction "1_1") (pintype "passive"))
      (node (ref "C20") (pin "1") (pinfunction "1_1") (pintype "passive"))
      (node (ref "D12") (pin "2") (pinfunction "2_2") (pintype "passive"))
      (node (ref "L1") (pin "1") (pinfunction "1_1") (pintype "passive"))
    )
    (net (code "36") (name "/WN1") (class "Default")
      (node (ref "C11") (pin "2") (pinfunction "2_2") (pintype "passive"))
      (node (ref "C5") (pin "2") (pinfunction "2_2") (pintype "passive"))
      (node (ref "C9") (pin "2") (pinfunction "2_2") (pintype "passive"))
      (node (ref "D1") (pin "2") (pinfunction "C_2") (pintype "passive"))
      (node (ref "D2") (pin "1") (pinfunction "A_1") (pintype "passive"))
      (node (ref "L1") (pin "3") (pinfunction "3_3") (pintype "passive"))
      (node (ref "R16") (pin "1") (pinfunction "1_1") (pintype "passive"))
      (node (ref "X1") (pin "2") (pinfunction "2_2") (pintype "passive"))
    )
    (net (code "37") (name "/WN2") (class "Default")
      (node (ref "C15") (pin "2") (pinfunction "2_2") (pintype "passive"))
      (node (ref "C21") (pin "2") (pinfunction "2_2") (pintype "passive"))
      (node (ref "D12") (pin "4") (pinfunction "4_4") (pintype "passive"))
      (node (ref "L1") (pin "4") (pinfunction "4_4") (pintype "passive"))
    )
    (net (code "38") (name "/W_H") (class "Default")
      (node (ref "R1") (pin "2") (pinfunction "2_2") (pintype "passive"))
      (node (ref "U1") (pin "21") (pinfunction "B0_21") (pintype "passive"))
    )
    (net (code "39") (name "/W_L") (class "Default")
      (node (ref "R4") (pin "2") (pinfunction "2_2") (pintype "passive"))
      (node (ref "U1") (pin "20") (pinfunction "B1_20") (pintype "passive"))
    )
    (net (code "40") (name "/ZCROSS") (class "Default")
      (node (ref "R45") (pin "1") (pinfunction "1_1") (pintype "passive"))
      (node (ref "X3") (pin "15") (pinfunction "15_15") (pintype "passive"))
    )
    (net (code "41") (name "DGND") (class "Default")
      (node (ref "B1") (pin "2") (pinfunction "2_2") (pintype "passive"))
      (node (ref "C1") (pin "2") (pinfunction "2_2") (pintype "passive"))
      (node (ref "C10") (pin "2") (pinfunction "2_2") (pintype "passive"))
      (node (ref "C12") (pin "2") (pinfunction "2_2") (pintype "passive"))
      (node (ref "C13") (pin "2") (pinfunction "2_2") (pintype "passive"))
      (node (ref "C14") (pin "2") (pinfunction "2_2") (pintype "passive"))
      (node (ref "C19") (pin "2") (pinfunction "2_2") (pintype "passive"))
      (node (ref "C2") (pin "2") (pinfunction "2_2") (pintype "passive"))
      (node (ref "C25") (pin "2") (pinfunction "2_2") (pintype "passive"))
      (node (ref "C26") (pin "1") (pinfunction "1_1") (pintype "passive"))
      (node (ref "C3") (pin "2") (pinfunction "2_2") (pintype "passive"))
      (node (ref "C33") (pin "2") (pinfunction "2_2") (pintype "passive"))
      (node (ref "C34") (pin "2") (pinfunction "2_2") (pintype "passive"))
      (node (ref "C37") (pin "2") (pinfunction "2_2") (pintype "passive"))
      (node (ref "C38") (pin "2") (pinfunction "2_2") (pintype "passive"))
      (node (ref "C4") (pin "2") (pinfunction "2_2") (pintype "passive"))
      (node (ref "C40") (pin "2") (pinfunction "2_2") (pintype "passive"))
      (node (ref "C41") (pin "2") (pinfunction "2_2") (pintype "passive"))
      (node (ref "C43") (pin "2") (pinfunction "2_2") (pintype "passive"))
      (node (ref "C44") (pin "2") (pinfunction "2_2") (pintype "passive"))
      (node (ref "C6") (pin "2") (pinfunction "2_2") (pintype "passive"))
      (node (ref "C7") (pin "2") (pinfunction "2_2") (pintype "passive"))
      (node (ref "D1") (pin "3") (pinfunction "E_3") (pintype "passive"))
      (node (ref "D13") (pin "1") (pinfunction "1_1") (pintype "passive"))
      (node (ref "D14") (pin "3") (pintype "passive"))
      (node (ref "D15") (pin "3") (pintype "passive"))
      (node (ref "D16") (pin "3") (pintype "passive"))
      (node (ref "D2") (pin "3") (pinfunction "E_3") (pintype "passive"))
      (node (ref "R30") (pin "2") (pinfunction "2_2") (pintype "passive"))
      (node (ref "R36") (pin "2") (pinfunction "2_2") (pintype "passive"))
      (node (ref "R42") (pin "2") (pinfunction "2_2") (pintype "passive"))
      (node (ref "U1") (pin "10") (pinfunction "A7_10") (pintype "passive"))
      (node (ref "U1") (pin "11") (pinfunction "GND_11") (pintype "passive"))
      (node (ref "U1") (pin "12") (pinfunction "GND_12") (pintype "passive"))
      (node (ref "U1") (pin "13") (pinfunction "GND_13") (pintype "passive"))
      (node (ref "U1") (pin "9") (pinfunction "A6_9") (pintype "passive"))
      (node (ref "U2") (pin "2") (pinfunction "COM_2") (pintype "passive"))
      (node (ref "U3") (pin "4") (pinfunction "A0_4") (pintype "passive"))
      (node (ref "U3") (pin "6") (pinfunction "GND_6") (pintype "passive"))
      (node (ref "U4") (pin "2") (pinfunction "GND_2") (pintype "passive"))
      (node (ref "U5") (pin "2") (pinfunction "GND_2") (pintype "passive"))
      (node (ref "U6") (pin "2") (pinfunction "GND_2") (pintype "passive"))
      (node (ref "X2") (pin "1") (pinfunction "1_1") (pintype "passive"))
      (node (ref "X2") (pin "11") (pinfunction "11_11") (pintype "passive"))
      (node (ref "X2") (pin "3") (pinfunction "3_3") (pintype "passive"))
      (node (ref "X2") (pin "5") (pinfunction "5_5") (pintype "passive"))
      (node (ref "X2") (pin "7") (pinfunction "7_7") (pintype "passive"))
      (node (ref "X2") (pin "9") (pinfunction "9_9") (pintype "passive"))
      (node (ref "X3") (pin "1") (pinfunction "1_1") (pintype "passive"))
      (node (ref "X3") (pin "3") (pinfunction "3_3") (pintype "passive"))
      (node (ref "X3") (pin "5") (pinfunction "5_5") (pintype "passive"))
      (node (ref "X3") (pin "7") (pinfunction "7_7") (pintype "passive"))
      (node (ref "X3") (pin "9") (pinfunction "9_9") (pintype "passive"))
    )
    (net (code "42") (name "HVBUS") (class "Default")
      (node (ref "C35") (pin "1") (pinfunction "1_1") (pintype "passive"))
      (node (ref "K4") (pin "1") (pinfunction "1_1") (pintype "passive"))
      (node (ref "U2") (pin "27") (pinfunction "P_27") (pintype "passive"))
    )
    (net (code "43") (name "Net-(C38-Pad1)") (class "Default")
      (node (ref "C38") (pin "1") (pinfunction "1_1") (pintype "passive"))
      (node (ref "D14") (pin "1") (pintype "passive"))
      (node (ref "D14") (pin "2") (pintype "passive"))
      (node (ref "R29") (pin "2") (pinfunction "2_2") (pintype "passive"))
      (node (ref "R30") (pin "1") (pinfunction "1_1") (pintype "passive"))
      (node (ref "R31") (pin "1") (pinfunction "1_1") (pintype "passive"))
    )
    (net (code "44") (name "Net-(C40-Pad1)") (class "Default")
      (node (ref "C40") (pin "1") (pinfunction "1_1") (pintype "passive"))
      (node (ref "D15") (pin "1") (pintype "passive"))
      (node (ref "D15") (pin "2") (pintype "passive"))
      (node (ref "R35") (pin "2") (pinfunction "2_2") (pintype "passive"))
      (node (ref "R36") (pin "1") (pinfunction "1_1") (pintype "passive"))
      (node (ref "R37") (pin "1") (pinfunction "1_1") (pintype "passive"))
    )
    (net (code "45") (name "Net-(C43-Pad1)") (class "Default")
      (node (ref "C43") (pin "1") (pinfunction "1_1") (pintype "passive"))
      (node (ref "D16") (pin "1") (pintype "passive"))
      (node (ref "D16") (pin "2") (pintype "passive"))
      (node (ref "R41") (pin "2") (pinfunction "2_2") (pintype "passive"))
      (node (ref "R42") (pin "1") (pinfunction "1_1") (pintype "passive"))
      (node (ref "R43") (pin "1") (pinfunction "1_1") (pintype "passive"))
    )
    (net (code "46") (name "Net-(D1-A)") (class "Default")
      (node (ref "C5") (pin "1") (pinfunction "1_1") (pintype "passive"))
      (node (ref "D1") (pin "1") (pinfunction "A_1") (pintype "passive"))
      (node (ref "D2") (pin "2") (pinfunction "C_2") (pintype "passive"))
      (node (ref "R7") (pin "2") (pinfunction "2_2") (pintype "passive"))
    )
    (net (code "47") (name "Net-(D1-C-Pad4)") (class "Default")
      (node (ref "D1") (pin "4") (pinfunction "C_4") (pintype "passive"))
      (node (ref "D2") (pin "4") (pinfunction "C_4") (pintype "passive"))
      (node (ref "R17") (pin "1") (pinfunction "1_1") (pintype "passive"))
      (node (ref "R45") (pin "2") (pinfunction "2_2") (pintype "passive"))
    )
    (net (code "48") (name "Net-(D9-C)") (class "Default")
      (node (ref "D9") (pin "1") (pinfunction "C_1") (pintype "passive"))
      (node (ref "R18") (pin "1") (pinfunction "1_1") (pintype "passive"))
    )
    (net (code "49") (name "Net-(D10-C)") (class "Default")
      (node (ref "D10") (pin "1") (pinfunction "C_1") (pintype "passive"))
      (node (ref "R19") (pin "1") (pinfunction "1_1") (pintype "passive"))
    )
    (net (code "50") (name "Net-(D11-C)") (class "Default")
      (node (ref "D11") (pin "1") (pinfunction "C_1") (pintype "passive"))
      (node (ref "R20") (pin "1") (pinfunction "1_1") (pintype "passive"))
    )
    (net (code "51") (name "Net-(D12-Pad1)") (class "Default")
      (node (ref "D12") (pin "1") (pinfunction "1_1") (pintype "passive"))
      (node (ref "K1") (pin "1") (pinfunction "1_1") (pintype "passive"))
    )
    (net (code "52") (name "Net-(D12-Pad3)") (class "Default")
      (node (ref "D12") (pin "3") (pinfunction "3_3") (pintype "passive"))
      (node (ref "K2") (pin "1") (pinfunction "1_1") (pintype "passive"))
    )
    (net (code "53") (name "Net-(R7-Pad1)") (class "Default")
      (node (ref "R7") (pin "1") (pinfunction "1_1") (pintype "passive"))
      (node (ref "R8") (pin "2") (pinfunction "2_2") (pintype "passive"))
    )
    (net (code "54") (name "Net-(R27-Pad2)") (class "Default")
      (node (ref "R27") (pin "2") (pinfunction "2_2") (pintype "passive"))
      (node (ref "R28") (pin "1") (pinfunction "1_1") (pintype "passive"))
    )
    (net (code "55") (name "Net-(R28-Pad2)") (class "Default")
      (node (ref "R28") (pin "2") (pinfunction "2_2") (pintype "passive"))
      (node (ref "R29") (pin "1") (pinfunction "1_1") (pintype "passive"))
    )
    (net (code "56") (name "Net-(R33-Pad2)") (class "Default")
      (node (ref "R33") (pin "2") (pinfunction "2_2") (pintype "passive"))
      (node (ref "R34") (pin "1") (pinfunction "1_1") (pintype "passive"))
    )
    (net (code "57") (name "Net-(R34-Pad2)") (class "Default")
      (node (ref "R34") (pin "2") (pinfunction "2_2") (pintype "passive"))
      (node (ref "R35") (pin "1") (pinfunction "1_1") (pintype "passive"))
    )
    (net (code "58") (name "Net-(R39-Pad2)") (class "Default")
      (node (ref "R39") (pin "2") (pinfunction "2_2") (pintype "passive"))
      (node (ref "R40") (pin "1") (pinfunction "1_1") (pintype "passive"))
    )
    (net (code "59") (name "Net-(R40-Pad2)") (class "Default")
      (node (ref "R40") (pin "2") (pinfunction "2_2") (pintype "passive"))
      (node (ref "R41") (pin "1") (pinfunction "1_1") (pintype "passive"))
    )
    (net (code "60") (name "Net-(U2-CFOD)") (class "Default")
      (node (ref "C33") (pin "1") (pinfunction "1_1") (pintype "passive"))
      (node (ref "U2") (pin "7") (pinfunction "CFOD_7") (pintype "passive"))
    )
    (net (code "61") (name "Net-(U2-CSC)") (class "Default")
      (node (ref "C34") (pin "1") (pinfunction "1_1") (pintype "passive"))
      (node (ref "R24") (pin "1") (pinfunction "1_1") (pintype "passive"))
      (node (ref "U2") (pin "8") (pinfunction "CSC_8") (pintype "passive"))
    )
    (net (code "62") (name "Net-(U2-NU)") (class "Default")
      (node (ref "R24") (pin "2") (pinfunction "2_2") (pintype "passive"))
      (node (ref "R25") (pin "2") (pinfunction "2_2") (pintype "passive"))
      (node (ref "U2") (pin "21") (pinfunction "NU_21") (pintype "passive"))
      (node (ref "U2") (pin "22") (pinfunction "NV_22") (pintype "passive"))
      (node (ref "U2") (pin "23") (pinfunction "NW_23") (pintype "passive"))
    )
    (net (code "63") (name "Net-(U2-VB(U))") (class "Default")
      (node (ref "C18") (pin "1") (pinfunction "1_1") (pintype "passive"))
      (node (ref "C24") (pin "1") (pinfunction "1_1") (pintype "passive"))
      (node (ref "C29") (pin "1") (pinfunction "1_1") (pintype "passive"))
      (node (ref "C32") (pin "1") (pinfunction "1_1") (pintype "passive"))
      (node (ref "R20") (pin "2") (pinfunction "2_2") (pintype "passive"))
      (node (ref "U2") (pin "11") (pinfunction "VB(U)_11") (pintype "passive"))
    )
    (net (code "64") (name "Net-(U2-VB(V))") (class "Default")
      (node (ref "C17") (pin "1") (pinfunction "1_1") (pintype "passive"))
      (node (ref "C23") (pin "1") (pinfunction "1_1") (pintype "passive"))
      (node (ref "C28") (pin "1") (pinfunction "1_1") (pintype "passive"))
      (node (ref "C31") (pin "1") (pinfunction "1_1") (pintype "passive"))
      (node (ref "R19") (pin "2") (pinfunction "2_2") (pintype "passive"))
      (node (ref "U2") (pin "15") (pinfunction "VB(V)_15") (pintype "passive"))
    )
    (net (code "65") (name "Net-(U2-VB(W))") (class "Default")
      (node (ref "C16") (pin "1") (pinfunction "1_1") (pintype "passive"))
      (node (ref "C22") (pin "1") (pinfunction "1_1") (pintype "passive"))
      (node (ref "C27") (pin "1") (pinfunction "1_1") (pintype "passive"))
      (node (ref "C30") (pin "1") (pinfunction "1_1") (pintype "passive"))
      (node (ref "R18") (pin "2") (pinfunction "2_2") (pintype "passive"))
      (node (ref "U2") (pin "19") (pinfunction "VB(W)_19") (pintype "passive"))
    )
    (net (code "66") (name "Net-(U2-VS(U))") (class "Default")
      (node (ref "C18") (pin "2") (pinfunction "2_2") (pintype "passive"))
      (node (ref "C24") (pin "2") (pinfunction "2_2") (pintype "passive"))
      (node (ref "C29") (pin "2") (pinfunction "2_2") (pintype "passive"))
      (node (ref "C32") (pin "2") (pinfunction "2_2") (pintype "passive"))
      (node (ref "U2") (pin "12") (pinfunction "VS(U)_12") (pintype "passive"))
    )
    (net (code "67") (name "Net-(U2-VS(V))") (class "Default")
      (node (ref "C17") (pin "2") (pinfunction "2_2") (pintype "passive"))
      (node (ref "C23") (pin "2") (pinfunction "2_2") (pintype "passive"))
      (node (ref "C28") (pin "2") (pinfunction "2_2") (pintype "passive"))
      (node (ref "C31") (pin "2") (pinfunction "2_2") (pintype "passive"))
      (node (ref "U2") (pin "16") (pinfunction "VS(V)_16") (pintype "passive"))
    )
    (net (code "68") (name "Net-(U2-VS(W))") (class "Default")
      (node (ref "C16") (pin "2") (pinfunction "2_2") (pintype "passive"))
      (node (ref "C22") (pin "2") (pinfunction "2_2") (pintype "passive"))
      (node (ref "C27") (pin "2") (pinfunction "2_2") (pintype "passive"))
      (node (ref "C30") (pin "2") (pinfunction "2_2") (pintype "passive"))
      (node (ref "U2") (pin "20") (pinfunction "VS(W)_20") (pintype "passive"))
    )
    (net (code "69") (name "Net-(U3-OS)") (class "Default")
      (node (ref "R44") (pin "1") (pinfunction "1_1") (pintype "passive"))
      (node (ref "U3") (pin "5") (pinfunction "OS_5") (pintype "passive"))
    )
    (net (code "70") (name "PE") (class "Default")
      (node (ref "C20") (pin "2") (pinfunction "2_2") (pintype "passive"))
      (node (ref "C21") (pin "1") (pinfunction "1_1") (pintype "passive"))
      (node (ref "C8") (pin "2") (pinfunction "2_2") (pintype "passive"))
      (node (ref "C9") (pin "1") (pinfunction "1_1") (pintype "passive"))
      (node (ref "X1") (pin "1") (pinfunction "1_1") (pintype "passive"))
    )
    (net (code "71") (name "PGND") (class "Default")
      (node (ref "B1") (pin "1") (pinfunction "1_1") (pintype "passive"))
      (node (ref "C35") (pin "2") (pinfunction "2_2") (pintype "passive"))
      (node (ref "K3") (pin "1") (pinfunction "1_1") (pintype "passive"))
      (node (ref "R25") (pin "1") (pinfunction "1_1") (pintype "passive"))
    )
    (net (code "72") (name "V5V") (class "Default")
      (node (ref "C3") (pin "1") (pinfunction "1_1") (pintype "passive"))
      (node (ref "U1") (pin "24") (pinfunction "VCCB_24") (pintype "passive"))
      (node (ref "X2") (pin "13") (pinfunction "13_13") (pintype "passive"))
    )
    (net (code "73") (name "V15V") (class "Default")
      (node (ref "C13") (pin "1") (pinfunction "1_1") (pintype "passive"))
      (node (ref "C14") (pin "1") (pinfunction "1_1") (pintype "passive"))
      (node (ref "C19") (pin "1") (pinfunction "1_1") (pintype "passive"))
      (node (ref "C25") (pin "1") (pinfunction "1_1") (pintype "passive"))
      (node (ref "D10") (pin "2") (pinfunction "A_2") (pintype "passive"))
      (node (ref "D11") (pin "2") (pinfunction "A_2") (pintype "passive"))
      (node (ref "D13") (pin "2") (pinfunction "2_2") (pintype "passive"))
      (node (ref "D9") (pin "2") (pinfunction "A_2") (pintype "passive"))
      (node (ref "U2") (pin "1") (pinfunction "VCCL_1") (pintype "passive"))
      (node (ref "U2") (pin "10") (pinfunction "VCCH_10") (pintype "passive"))
      (node (ref "U2") (pin "14") (pinfunction "VCCH_14") (pintype "passive"))
      (node (ref "U2") (pin "18") (pinfunction "VCCH_18") (pintype "passive"))
      (node (ref "X2") (pin "15") (pinfunction "15_15") (pintype "passive"))
    )
    (net (code "74") (name "VDDC") (class "Default")
      (node (ref "C1") (pin "1") (pinfunction "1_1") (pintype "passive"))
      (node (ref "C37") (pin "1") (pinfunction "1_1") (pintype "passive"))
      (node (ref "C41") (pin "1") (pinfunction "1_1") (pintype "passive"))
      (node (ref "C44") (pin "1") (pinfunction "1_1") (pintype "passive"))
      (node (ref "R17") (pin "2") (pinfunction "2_2") (pintype "passive"))
      (node (ref "U1") (pin "1") (pinfunction "VCCA_1") (pintype "power_in"))
      (node (ref "U1") (pin "2") (pinfunction "T/~{R}_2") (pintype "input"))
      (node (ref "U3") (pin "2") (pinfunction "VDD_2") (pintype "passive"))
      (node (ref "U4") (pin "1") (pinfunction "VCC_1") (pintype "passive"))
      (node (ref "U5") (pin "1") (pinfunction "VCC_1") (pintype "passive"))
      (node (ref "U6") (pin "1") (pinfunction "VCC_1") (pintype "passive"))
      (node (ref "X3") (pin "11") (pinfunction "11_11") (pintype "passive"))
    )
    (net (code "75") (name "unconnected-(U1-B6-Pad15)") (class "Default")
      (node (ref "U1") (pin "15") (pinfunction "B6_15") (pintype "passive"))
    )
    (net (code "76") (name "unconnected-(U1-B7-Pad14)") (class "Default")
      (node (ref "U1") (pin "14") (pinfunction "B7_14") (pintype "passive"))
    )
    (net (code "77") (name "unconnected-(U1-NC-Pad23)") (class "Default")
      (node (ref "U1") (pin "23") (pinfunction "NC_23") (pintype "passive"))
    )
  )
)
